# atmega328_5v_16mhz.net
KiCad netlist of a schematic drawn in EAGLE
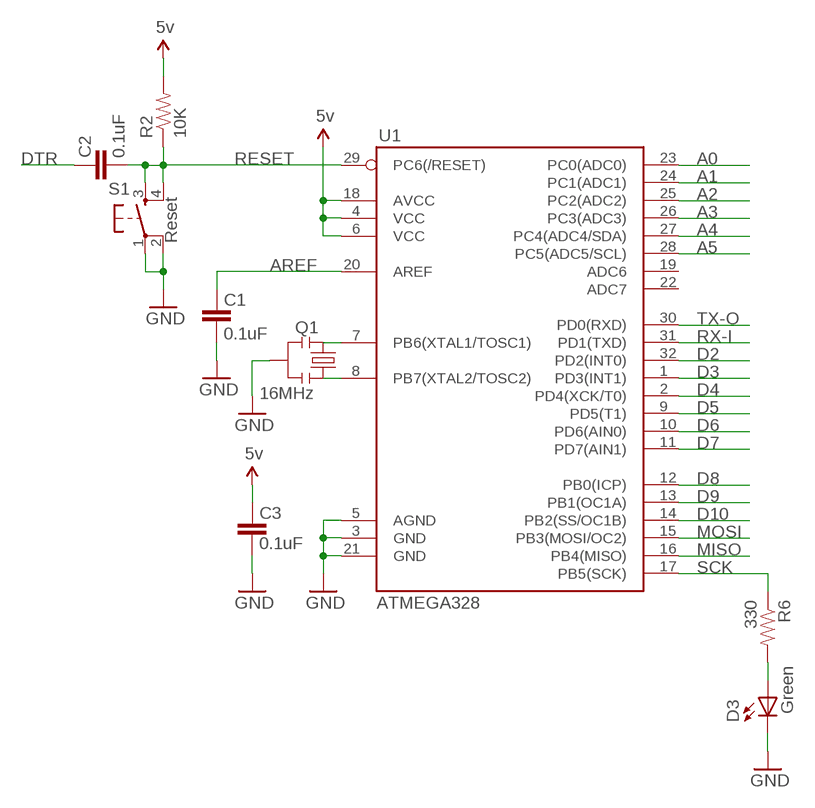
[diagram p0: schematic, sheet 1]

(export (version "E")
  (design (tool "Eeschema 10.0.6"))
  (components
    (comp (ref "C1")
      (value "0.1uF")
      (footprint "eagle-import:0402-CAP")
      (libsource (lib "eagle-import") (part "CAP0402-CAP"))
    )
    (comp (ref "C2")
      (value "0.1uF")
      (footprint "eagle-import:0402-CAP")
      (libsource (lib "eagle-import") (part "CAP0402-CAP"))
    )
    (comp (ref "C3")
      (value "0.1uF")
      (footprint "eagle-import:0402-CAP")
      (libsource (lib "eagle-import") (part "CAP0402-CAP"))
    )
    (comp (ref "D3")
      (value "Green")
      (footprint "eagle-import:LED-0603")
      (libsource (lib "eagle-import") (part "LED0603"))
    )
    (comp (ref "Q1")
      (value "16MHz")
      (footprint "eagle-import:RESONATOR-SMD")
      (libsource (lib "eagle-import") (part "RESONATORSMD"))
    )
    (comp (ref "R2")
      (value "10K")
      (footprint "eagle-import:0402-RES")
      (libsource (lib "eagle-import") (part "RESISTOR0402-RES"))
    )
    (comp (ref "R6")
      (value "330")
      (footprint "eagle-import:0402-RES")
      (libsource (lib "eagle-import") (part "RESISTOR0402-RES"))
    )
    (comp (ref "S1")
      (value "Reset")
      (footprint "eagle-import:TACTILE_SWITCH_SMD")
      (libsource (lib "eagle-import") (part "TAC_SWITCHSMD"))
    )
    (comp (ref "U1")
      (value "ATMEGA328")
      (footprint "eagle-import:TQFP32-08")
      (libsource (lib "eagle-import") (part "ATMEGA168"))
    )
  )
  (nets
    (net (code "1") (name "/A0") (class "Default")
      (node (ref "U1") (pin "23") (pinfunction "PC0(ADC0)_23") (pintype "bidirectional"))
    )
    (net (code "2") (name "/A1") (class "Default")
      (node (ref "U1") (pin "24") (pinfunction "PC1(ADC1)_24") (pintype "bidirectional"))
    )
    (net (code "3") (name "/A2") (class "Default")
      (node (ref "U1") (pin "25") (pinfunction "PC2(ADC2)_25") (pintype "bidirectional"))
    )
    (net (code "4") (name "/A3") (class "Default")
      (node (ref "U1") (pin "26") (pinfunction "PC3(ADC3)_26") (pintype "bidirectional"))
    )
    (net (code "5") (name "/A4") (class "Default")
      (node (ref "U1") (pin "27") (pinfunction "PC4(ADC4/SDA)_27") (pintype "bidirectional"))
    )
    (net (code "6") (name "/A5") (class "Default")
      (node (ref "U1") (pin "28") (pinfunction "PC5(ADC5/SCL)_28") (pintype "bidirectional"))
    )
    (net (code "7") (name "/AREF") (class "Default")
      (node (ref "C1") (pin "2") (pinfunction "2_2") (pintype "passive"))
      (node (ref "U1") (pin "20") (pinfunction "AREF_20") (pintype "bidirectional"))
    )
    (net (code "8") (name "/D2") (class "Default")
      (node (ref "U1") (pin "32") (pinfunction "PD2(INT0)_32") (pintype "bidirectional"))
    )
    (net (code "9") (name "/D3") (class "Default")
      (node (ref "U1") (pin "1") (pinfunction "PD3(INT1)_1") (pintype "bidirectional"))
    )
    (net (code "10") (name "/D4") (class "Default")
      (node (ref "U1") (pin "2") (pinfunction "PD4(XCK/T0)_2") (pintype "bidirectional"))
    )
    (net (code "11") (name "/D5") (class "Default")
      (node (ref "U1") (pin "9") (pinfunction "PD5(T1)_9") (pintype "bidirectional"))
    )
    (net (code "12") (name "/D6") (class "Default")
      (node (ref "U1") (pin "10") (pinfunction "PD6(AIN0)_10") (pintype "bidirectional"))
    )
    (net (code "13") (name "/D7") (class "Default")
      (node (ref "U1") (pin "11") (pinfunction "PD7(AIN1)_11") (pintype "bidirectional"))
    )
    (net (code "14") (name "/D8") (class "Default")
      (node (ref "U1") (pin "12") (pinfunction "PB0(ICP)_12") (pintype "bidirectional"))
    )
    (net (code "15") (name "/D9") (class "Default")
      (node (ref "U1") (pin "13") (pinfunction "PB1(OC1A)_13") (pintype "bidirectional"))
    )
    (net (code "16") (name "/D10") (class "Default")
      (node (ref "U1") (pin "14") (pinfunction "PB2(SS/OC1B)_14") (pintype "bidirectional"))
    )
    (net (code "17") (name "/DTR") (class "Default")
      (node (ref "C2") (pin "2") (pinfunction "2_2") (pintype "passive"))
    )
    (net (code "18") (name "/MISO") (class "Default")
      (node (ref "U1") (pin "16") (pinfunction "PB4(MISO)_16") (pintype "bidirectional"))
    )
    (net (code "19") (name "/MOSI") (class "Default")
      (node (ref "U1") (pin "15") (pinfunction "PB3(MOSI/OC2)_15") (pintype "bidirectional"))
    )
    (net (code "20") (name "/RESET") (class "Default")
      (node (ref "C2") (pin "1") (pinfunction "1_1") (pintype "passive"))
      (node (ref "R2") (pin "1") (pinfunction "1_1") (pintype "passive"))
      (node (ref "S1") (pin "3") (pinfunction "3_3") (pintype "passive"))
      (node (ref "S1") (pin "4") (pinfunction "4_4") (pintype "passive"))
      (node (ref "U1") (pin "29") (pinfunction "PC6(/RESET)_29") (pintype "bidirectional"))
    )
    (net (code "21") (name "/RX-I") (class "Default")
      (node (ref "U1") (pin "31") (pinfunction "PD1(TXD)_31") (pintype "bidirectional"))
    )
    (net (code "22") (name "/SCK") (class "Default")
      (node (ref "R6") (pin "1") (pinfunction "1_1") (pintype "passive"))
      (node (ref "U1") (pin "17") (pinfunction "PB5(SCK)_17") (pintype "bidirectional"))
    )
    (net (code "23") (name "/TX-O") (class "Default")
      (node (ref "U1") (pin "30") (pinfunction "PD0(RXD)_30") (pintype "bidirectional"))
    )
    (net (code "24") (name "5v") (class "Default")
      (node (ref "C3") (pin "2") (pinfunction "2_2") (pintype "passive"))
      (node (ref "R2") (pin "2") (pinfunction "2_2") (pintype "passive"))
      (node (ref "U1") (pin "18") (pinfunction "AVCC_18") (pintype "bidirectional"))
      (node (ref "U1") (pin "4") (pinfunction "VCC_4") (pintype "bidirectional"))
      (node (ref "U1") (pin "6") (pinfunction "VCC_6") (pintype "bidirectional"))
    )
    (net (code "25") (name "GND") (class "Default")
      (node (ref "C1") (pin "1") (pinfunction "1_1") (pintype "passive"))
      (node (ref "C3") (pin "1") (pinfunction "1_1") (pintype "passive"))
      (node (ref "D3") (pin "C") (pinfunction "C_C") (pintype "passive"))
      (node (ref "Q1") (pin "2") (pinfunction "2_2") (pintype "passive"))
      (node (ref "S1") (pin "1") (pinfunction "1_1") (pintype "passive"))
      (node (ref "S1") (pin "2") (pinfunction "2_2") (pintype "passive"))
      (node (ref "U1") (pin "21") (pinfunction "GND_21") (pintype "bidirectional"))
      (node (ref "U1") (pin "3") (pinfunction "GND_3") (pintype "bidirectional"))
      (node (ref "U1") (pin "5") (pinfunction "AGND_5") (pintype "bidirectional"))
    )
    (net (code "26") (name "Net-(D3-PadA)") (class "Default")
      (node (ref "D3") (pin "A") (pinfunction "A_A") (pintype "passive"))
      (node (ref "R6") (pin "2") (pinfunction "2_2") (pintype "passive"))
    )
    (net (code "27") (name "Net-(U1-PB6(XTAL1{slash}TOSC1))") (class "Default")
      (node (ref "Q1") (pin "3") (pinfunction "3_3") (pintype "passive"))
      (node (ref "U1") (pin "7") (pinfunction "PB6(XTAL1/TOSC1)_7") (pintype "bidirectional"))
    )
    (net (code "28") (name "Net-(U1-PB7(XTAL2{slash}TOSC2))") (class "Default")
      (node (ref "Q1") (pin "1") (pinfunction "1_1") (pintype "passive"))
      (node (ref "U1") (pin "8") (pinfunction "PB7(XTAL2/TOSC2)_8") (pintype "bidirectional"))
    )
    (net (code "29") (name "unconnected-(U1-ADC6-Pad19)") (class "Default")
      (node (ref "U1") (pin "19") (pinfunction "ADC6_19") (pintype "bidirectional"))
    )
    (net (code "30") (name "unconnected-(U1-ADC7-Pad22)") (class "Default")
      (node (ref "U1") (pin "22") (pinfunction "ADC7_22") (pintype "bidirectional"))
    )
  )
)
